# 7006268-0-0.net
KiCad netlist of a schematic drawn in EAGLE
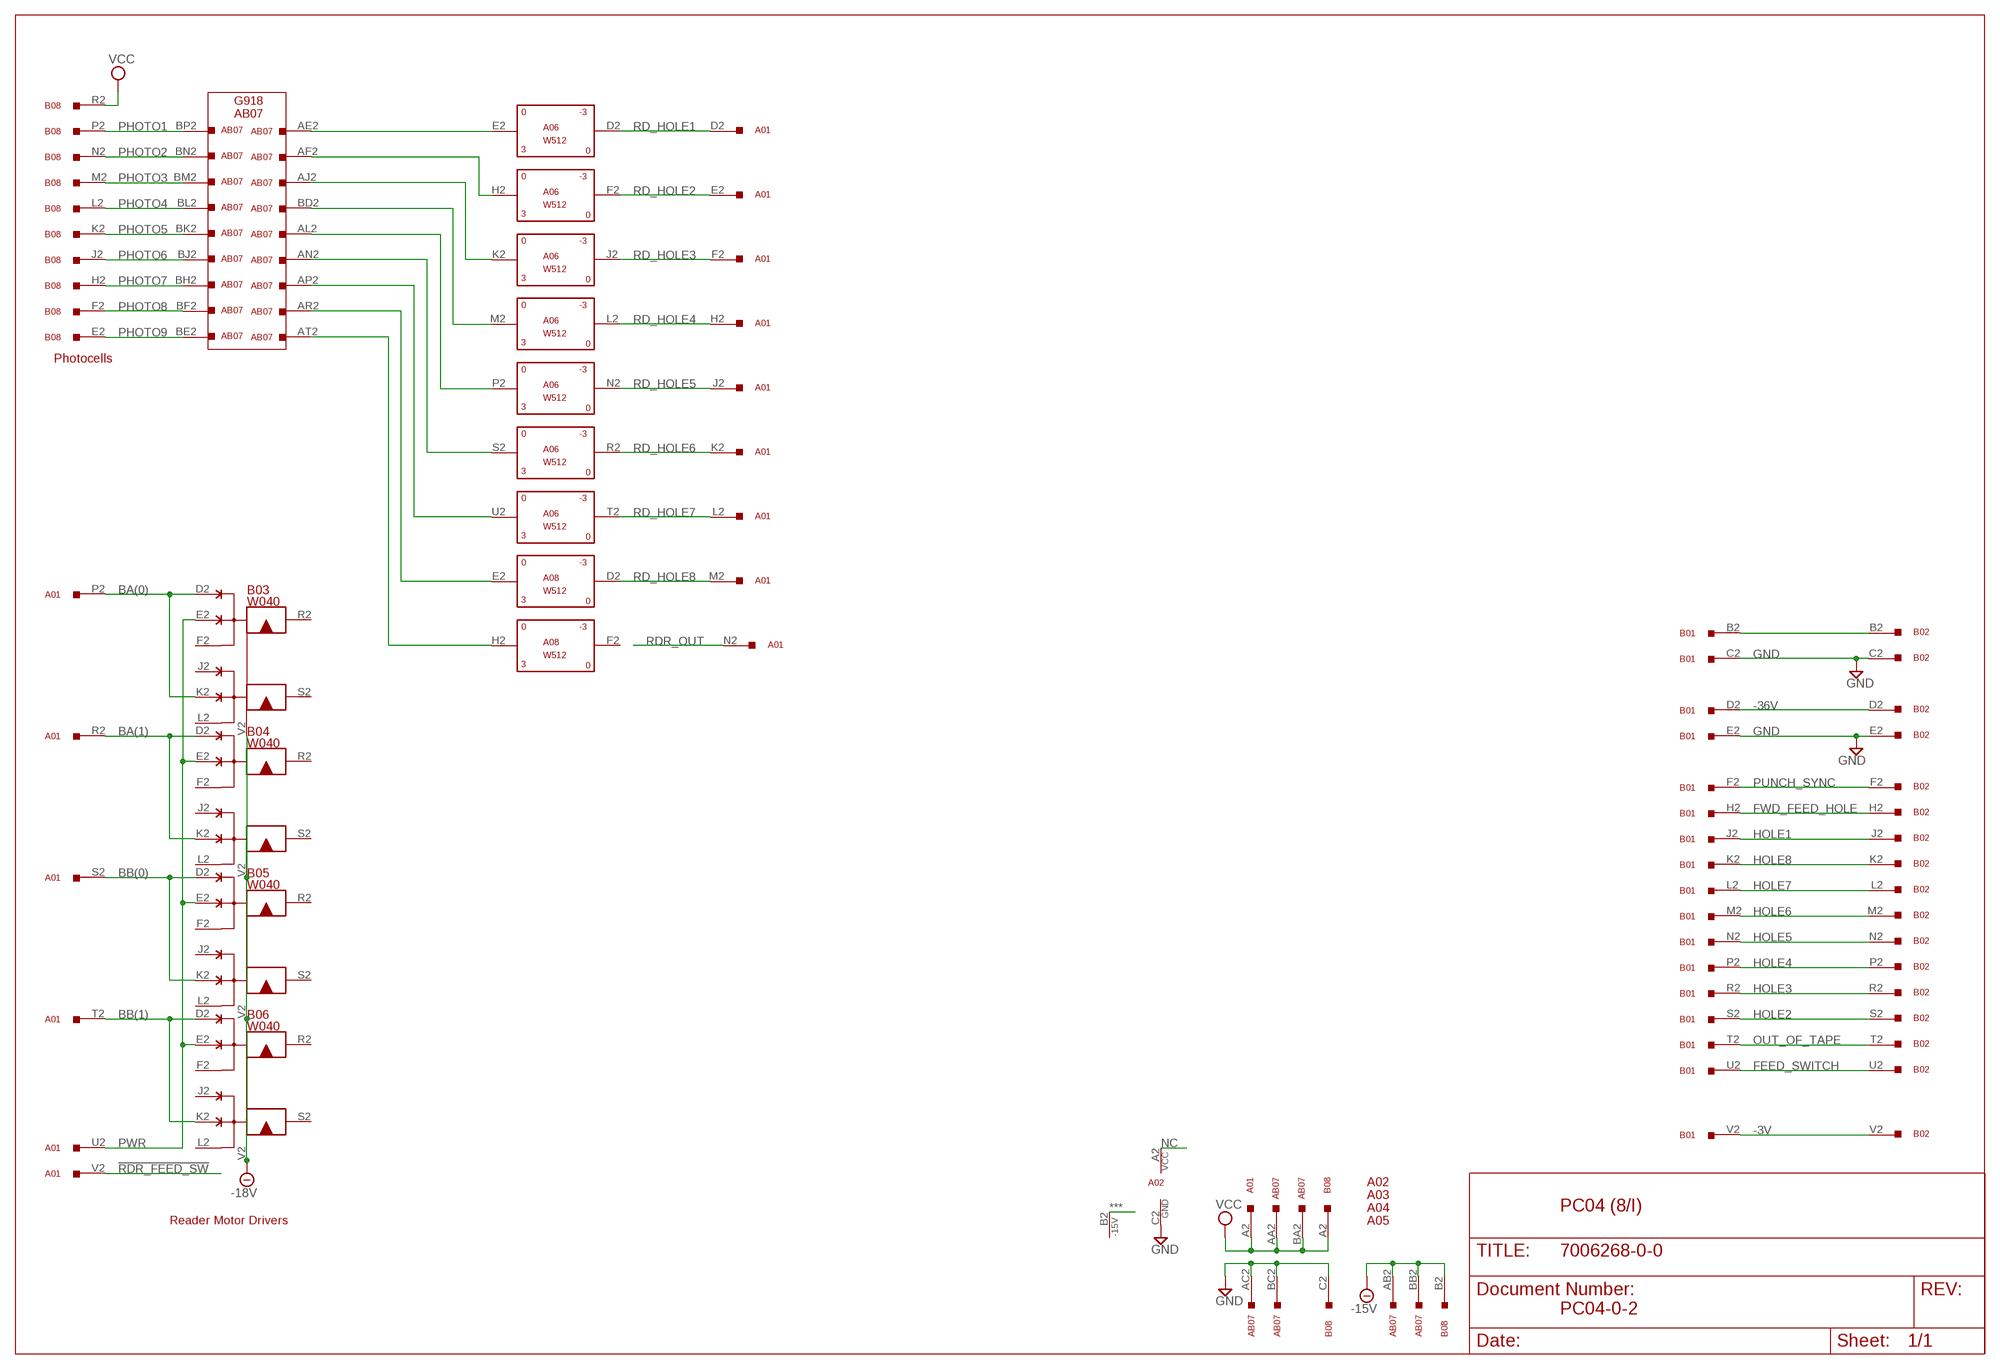
[diagram p0: schematic, sheet 1]

(export (version "E")
  (design (tool "Eeschema 10.0.6"))
  (components
    (comp (ref "A01")
      (value "W033")
      (footprint "eagle-import:H807")
      (libsource (lib "eagle-import") (part "W023"))
    )
    (comp (ref "A02")
      (value "EMPTY")
      (footprint "eagle-import:H807")
      (libsource (lib "eagle-import") (part "EMPTY"))
    )
    (comp (ref "A03")
      (value "EMPTY")
      (footprint "eagle-import:H807")
      (libsource (lib "eagle-import") (part "EMPTY"))
    )
    (comp (ref "A04")
      (value "EMPTY")
      (footprint "eagle-import:H807")
      (libsource (lib "eagle-import") (part "EMPTY"))
    )
    (comp (ref "A05")
      (value "EMPTY")
      (footprint "eagle-import:H807")
      (libsource (lib "eagle-import") (part "EMPTY"))
    )
    (comp (ref "A06")
      (value "W512")
      (footprint "eagle-import:H807")
      (libsource (lib "eagle-import") (part "W512"))
    )
    (comp (ref "A08")
      (value "W512")
      (footprint "eagle-import:H807")
      (libsource (lib "eagle-import") (part "W512"))
    )
    (comp (ref "AB07")
      (value "G918")
      (footprint "eagle-import:H807-2")
      (libsource (lib "eagle-import") (part "W991"))
    )
    (comp (ref "B01")
      (value "W033")
      (footprint "eagle-import:H807")
      (libsource (lib "eagle-import") (part "W023"))
    )
    (comp (ref "B02")
      (value "W033")
      (footprint "eagle-import:H807")
      (libsource (lib "eagle-import") (part "W023"))
    )
    (comp (ref "B03")
      (value "W040")
      (footprint "eagle-import:H807")
      (libsource (lib "eagle-import") (part "W040"))
    )
    (comp (ref "B04")
      (value "W040")
      (footprint "eagle-import:H807")
      (libsource (lib "eagle-import") (part "W040"))
    )
    (comp (ref "B05")
      (value "W040")
      (footprint "eagle-import:H807")
      (libsource (lib "eagle-import") (part "W040"))
    )
    (comp (ref "B06")
      (value "W040")
      (footprint "eagle-import:H807")
      (libsource (lib "eagle-import") (part "W040"))
    )
    (comp (ref "B08")
      (value "W033")
      (footprint "eagle-import:H807")
      (libsource (lib "eagle-import") (part "W023"))
    )
  )
  (nets
    (net (code "1") (name "-15V") (class "Default")
      (node (ref "AB07") (pin "AB2") (pinfunction "P$2_AB2") (pintype "bidirectional"))
      (node (ref "AB07") (pin "BB2") (pinfunction "P$2_BB2") (pintype "bidirectional"))
      (node (ref "B08") (pin "B2") (pinfunction "P$2_B2") (pintype "bidirectional"))
    )
    (net (code "2") (name "-18V") (class "Default")
      (node (ref "B03") (pin "V2") (pinfunction "V_V2") (pintype "input"))
      (node (ref "B04") (pin "V2") (pinfunction "V_V2") (pintype "input"))
      (node (ref "B05") (pin "V2") (pinfunction "V_V2") (pintype "input"))
      (node (ref "B06") (pin "V2") (pinfunction "V_V2") (pintype "input"))
    )
    (net (code "3") (name "/***") (class "Default")
      (node (ref "A02") (pin "B2") (pinfunction "-15V_B2") (pintype "power_in"))
    )
    (net (code "4") (name "/-3V") (class "Default")
      (node (ref "B01") (pin "V2") (pinfunction "P$2_V2") (pintype "bidirectional"))
      (node (ref "B02") (pin "V2") (pinfunction "P$2_V2") (pintype "bidirectional"))
    )
    (net (code "5") (name "/-36V") (class "Default")
      (node (ref "B01") (pin "D2") (pinfunction "P$2_D2") (pintype "bidirectional"))
      (node (ref "B02") (pin "D2") (pinfunction "P$2_D2") (pintype "bidirectional"))
    )
    (net (code "6") (name "/BA(0)") (class "Default")
      (node (ref "A01") (pin "P2") (pinfunction "P$2_P2") (pintype "bidirectional"))
      (node (ref "B03") (pin "D2") (pinfunction "D_D2") (pintype "input"))
      (node (ref "B03") (pin "K2") (pinfunction "K_K2") (pintype "input"))
    )
    (net (code "7") (name "/BA(1)") (class "Default")
      (node (ref "A01") (pin "R2") (pinfunction "P$2_R2") (pintype "bidirectional"))
      (node (ref "B04") (pin "D2") (pinfunction "D_D2") (pintype "input"))
      (node (ref "B04") (pin "K2") (pinfunction "K_K2") (pintype "input"))
    )
    (net (code "8") (name "/BB(0)") (class "Default")
      (node (ref "A01") (pin "S2") (pinfunction "P$2_S2") (pintype "bidirectional"))
      (node (ref "B05") (pin "D2") (pinfunction "D_D2") (pintype "input"))
      (node (ref "B05") (pin "K2") (pinfunction "K_K2") (pintype "input"))
    )
    (net (code "9") (name "/BB(1)") (class "Default")
      (node (ref "A01") (pin "T2") (pinfunction "P$2_T2") (pintype "bidirectional"))
      (node (ref "B06") (pin "D2") (pinfunction "D_D2") (pintype "input"))
      (node (ref "B06") (pin "K2") (pinfunction "K_K2") (pintype "input"))
    )
    (net (code "10") (name "/FEED_SWITCH") (class "Default")
      (node (ref "B01") (pin "U2") (pinfunction "P$2_U2") (pintype "bidirectional"))
      (node (ref "B02") (pin "U2") (pinfunction "P$2_U2") (pintype "bidirectional"))
    )
    (net (code "11") (name "/FWD_FEED_HOLE") (class "Default")
      (node (ref "B01") (pin "H2") (pinfunction "P$2_H2") (pintype "bidirectional"))
      (node (ref "B02") (pin "H2") (pinfunction "P$2_H2") (pintype "bidirectional"))
    )
    (net (code "12") (name "/HOLE1") (class "Default")
      (node (ref "B01") (pin "J2") (pinfunction "P$2_J2") (pintype "bidirectional"))
      (node (ref "B02") (pin "J2") (pinfunction "P$2_J2") (pintype "bidirectional"))
    )
    (net (code "13") (name "/HOLE2") (class "Default")
      (node (ref "B01") (pin "S2") (pinfunction "P$2_S2") (pintype "bidirectional"))
      (node (ref "B02") (pin "S2") (pinfunction "P$2_S2") (pintype "bidirectional"))
    )
    (net (code "14") (name "/HOLE3") (class "Default")
      (node (ref "B01") (pin "R2") (pinfunction "P$2_R2") (pintype "bidirectional"))
      (node (ref "B02") (pin "R2") (pinfunction "P$2_R2") (pintype "bidirectional"))
    )
    (net (code "15") (name "/HOLE4") (class "Default")
      (node (ref "B01") (pin "P2") (pinfunction "P$2_P2") (pintype "bidirectional"))
      (node (ref "B02") (pin "P2") (pinfunction "P$2_P2") (pintype "bidirectional"))
    )
    (net (code "16") (name "/HOLE5") (class "Default")
      (node (ref "B01") (pin "N2") (pinfunction "P$2_N2") (pintype "bidirectional"))
      (node (ref "B02") (pin "N2") (pinfunction "P$2_N2") (pintype "bidirectional"))
    )
    (net (code "17") (name "/HOLE6") (class "Default")
      (node (ref "B01") (pin "M2") (pinfunction "P$2_M2") (pintype "bidirectional"))
      (node (ref "B02") (pin "M2") (pinfunction "P$2_M2") (pintype "bidirectional"))
    )
    (net (code "18") (name "/HOLE7") (class "Default")
      (node (ref "B01") (pin "L2") (pinfunction "P$2_L2") (pintype "bidirectional"))
      (node (ref "B02") (pin "L2") (pinfunction "P$2_L2") (pintype "bidirectional"))
    )
    (net (code "19") (name "/HOLE8") (class "Default")
      (node (ref "B01") (pin "K2") (pinfunction "P$2_K2") (pintype "bidirectional"))
      (node (ref "B02") (pin "K2") (pinfunction "P$2_K2") (pintype "bidirectional"))
    )
    (net (code "20") (name "/NC") (class "Default")
      (node (ref "A02") (pin "A2") (pinfunction "VCC_A2") (pintype "power_in"))
    )
    (net (code "21") (name "/OUT_OF_TAPE") (class "Default")
      (node (ref "B01") (pin "T2") (pinfunction "P$2_T2") (pintype "bidirectional"))
      (node (ref "B02") (pin "T2") (pinfunction "P$2_T2") (pintype "bidirectional"))
    )
    (net (code "22") (name "/PHOTO1") (class "Default")
      (node (ref "AB07") (pin "BP2") (pinfunction "P$2_BP2") (pintype "bidirectional"))
      (node (ref "B08") (pin "P2") (pinfunction "P$2_P2") (pintype "bidirectional"))
    )
    (net (code "23") (name "/PHOTO2") (class "Default")
      (node (ref "AB07") (pin "BN2") (pinfunction "P$2_BN2") (pintype "bidirectional"))
      (node (ref "B08") (pin "N2") (pinfunction "P$2_N2") (pintype "bidirectional"))
    )
    (net (code "24") (name "/PHOTO3") (class "Default")
      (node (ref "AB07") (pin "BM2") (pinfunction "P$2_BM2") (pintype "bidirectional"))
      (node (ref "B08") (pin "M2") (pinfunction "P$2_M2") (pintype "bidirectional"))
    )
    (net (code "25") (name "/PHOTO4") (class "Default")
      (node (ref "AB07") (pin "BL2") (pinfunction "P$2_BL2") (pintype "bidirectional"))
      (node (ref "B08") (pin "L2") (pinfunction "P$2_L2") (pintype "bidirectional"))
    )
    (net (code "26") (name "/PHOTO5") (class "Default")
      (node (ref "AB07") (pin "BK2") (pinfunction "P$2_BK2") (pintype "bidirectional"))
      (node (ref "B08") (pin "K2") (pinfunction "P$2_K2") (pintype "bidirectional"))
    )
    (net (code "27") (name "/PHOTO6") (class "Default")
      (node (ref "AB07") (pin "BJ2") (pinfunction "P$2_BJ2") (pintype "bidirectional"))
      (node (ref "B08") (pin "J2") (pinfunction "P$2_J2") (pintype "bidirectional"))
    )
    (net (code "28") (name "/PHOTO7") (class "Default")
      (node (ref "AB07") (pin "BH2") (pinfunction "P$2_BH2") (pintype "bidirectional"))
      (node (ref "B08") (pin "H2") (pinfunction "P$2_H2") (pintype "bidirectional"))
    )
    (net (code "29") (name "/PHOTO8") (class "Default")
      (node (ref "AB07") (pin "BF2") (pinfunction "P$2_BF2") (pintype "bidirectional"))
      (node (ref "B08") (pin "F2") (pinfunction "P$2_F2") (pintype "bidirectional"))
    )
    (net (code "30") (name "/PHOTO9") (class "Default")
      (node (ref "AB07") (pin "BE2") (pinfunction "P$2_BE2") (pintype "bidirectional"))
      (node (ref "B08") (pin "E2") (pinfunction "P$2_E2") (pintype "bidirectional"))
    )
    (net (code "31") (name "/PUNCH_SYNC") (class "Default")
      (node (ref "B01") (pin "F2") (pinfunction "P$2_F2") (pintype "bidirectional"))
      (node (ref "B02") (pin "F2") (pinfunction "P$2_F2") (pintype "bidirectional"))
    )
    (net (code "32") (name "/PWR") (class "Default")
      (node (ref "A01") (pin "U2") (pinfunction "P$2_U2") (pintype "bidirectional"))
      (node (ref "B03") (pin "E2") (pinfunction "E_E2") (pintype "input"))
      (node (ref "B04") (pin "E2") (pinfunction "E_E2") (pintype "input"))
      (node (ref "B05") (pin "E2") (pinfunction "E_E2") (pintype "input"))
      (node (ref "B06") (pin "E2") (pinfunction "E_E2") (pintype "input"))
    )
    (net (code "33") (name "/RDR_OUT") (class "Default")
      (node (ref "A01") (pin "N2") (pinfunction "P$2_N2") (pintype "bidirectional"))
    )
    (net (code "34") (name "/RD_HOLE1") (class "Default")
      (node (ref "A01") (pin "D2") (pinfunction "P$2_D2") (pintype "bidirectional"))
      (node (ref "A06") (pin "D2") (pinfunction "OUT_D2") (pintype "output"))
    )
    (net (code "35") (name "/RD_HOLE2") (class "Default")
      (node (ref "A01") (pin "E2") (pinfunction "P$2_E2") (pintype "bidirectional"))
      (node (ref "A06") (pin "F2") (pinfunction "OUT_F2") (pintype "output"))
    )
    (net (code "36") (name "/RD_HOLE3") (class "Default")
      (node (ref "A01") (pin "F2") (pinfunction "P$2_F2") (pintype "bidirectional"))
      (node (ref "A06") (pin "J2") (pinfunction "OUT_J2") (pintype "output"))
    )
    (net (code "37") (name "/RD_HOLE4") (class "Default")
      (node (ref "A01") (pin "H2") (pinfunction "P$2_H2") (pintype "bidirectional"))
      (node (ref "A06") (pin "L2") (pinfunction "OUT_L2") (pintype "output"))
    )
    (net (code "38") (name "/RD_HOLE5") (class "Default")
      (node (ref "A01") (pin "J2") (pinfunction "P$2_J2") (pintype "bidirectional"))
      (node (ref "A06") (pin "N2") (pinfunction "OUT_N2") (pintype "output"))
    )
    (net (code "39") (name "/RD_HOLE6") (class "Default")
      (node (ref "A01") (pin "K2") (pinfunction "P$2_K2") (pintype "bidirectional"))
      (node (ref "A06") (pin "R2") (pinfunction "OUT_R2") (pintype "output"))
    )
    (net (code "40") (name "/RD_HOLE7") (class "Default")
      (node (ref "A01") (pin "L2") (pinfunction "P$2_L2") (pintype "bidirectional"))
      (node (ref "A06") (pin "T2") (pinfunction "OUT_T2") (pintype "output"))
    )
    (net (code "41") (name "/RD_HOLE8") (class "Default")
      (node (ref "A01") (pin "M2") (pinfunction "P$2_M2") (pintype "bidirectional"))
      (node (ref "A08") (pin "D2") (pinfunction "OUT_D2") (pintype "output"))
    )
    (net (code "42") (name "/~{RDR_FEED_SW}") (class "Default")
      (node (ref "A01") (pin "V2") (pinfunction "P$2_V2") (pintype "bidirectional"))
    )
    (net (code "43") (name "GND") (class "Default")
      (node (ref "A02") (pin "C2") (pinfunction "GND_C2") (pintype "power_in"))
      (node (ref "AB07") (pin "AC2") (pinfunction "P$2_AC2") (pintype "bidirectional"))
      (node (ref "AB07") (pin "BC2") (pinfunction "P$2_BC2") (pintype "bidirectional"))
      (node (ref "B01") (pin "C2") (pinfunction "P$2_C2") (pintype "bidirectional"))
      (node (ref "B01") (pin "E2") (pinfunction "P$2_E2") (pintype "bidirectional"))
      (node (ref "B02") (pin "C2") (pinfunction "P$2_C2") (pintype "bidirectional"))
      (node (ref "B02") (pin "E2") (pinfunction "P$2_E2") (pintype "bidirectional"))
      (node (ref "B08") (pin "C2") (pinfunction "P$2_C2") (pintype "bidirectional"))
    )
    (net (code "44") (name "Net-(A06A-IN)") (class "Default")
      (node (ref "A06") (pin "E2") (pinfunction "IN_E2") (pintype "input"))
      (node (ref "AB07") (pin "AE2") (pinfunction "P$2_AE2") (pintype "bidirectional"))
    )
    (net (code "45") (name "Net-(A06B-IN)") (class "Default")
      (node (ref "A06") (pin "H2") (pinfunction "IN_H2") (pintype "input"))
      (node (ref "AB07") (pin "AF2") (pinfunction "P$2_AF2") (pintype "bidirectional"))
    )
    (net (code "46") (name "Net-(A06E-IN)") (class "Default")
      (node (ref "A06") (pin "K2") (pinfunction "IN_K2") (pintype "input"))
      (node (ref "AB07") (pin "AJ2") (pinfunction "P$2_AJ2") (pintype "bidirectional"))
    )
    (net (code "47") (name "Net-(A06F-IN)") (class "Default")
      (node (ref "A06") (pin "M2") (pinfunction "IN_M2") (pintype "input"))
      (node (ref "AB07") (pin "BD2") (pinfunction "P$2_BD2") (pintype "bidirectional"))
    )
    (net (code "48") (name "Net-(A06G-IN)") (class "Default")
      (node (ref "A06") (pin "P2") (pinfunction "IN_P2") (pintype "input"))
      (node (ref "AB07") (pin "AL2") (pinfunction "P$2_AL2") (pintype "bidirectional"))
    )
    (net (code "49") (name "Net-(A06H-IN)") (class "Default")
      (node (ref "A06") (pin "S2") (pinfunction "IN_S2") (pintype "input"))
      (node (ref "AB07") (pin "AN2") (pinfunction "P$2_AN2") (pintype "bidirectional"))
    )
    (net (code "50") (name "Net-(A06I-IN)") (class "Default")
      (node (ref "A06") (pin "U2") (pinfunction "IN_U2") (pintype "input"))
      (node (ref "AB07") (pin "AP2") (pinfunction "P$2_AP2") (pintype "bidirectional"))
    )
    (net (code "51") (name "Net-(A08A-IN)") (class "Default")
      (node (ref "A08") (pin "E2") (pinfunction "IN_E2") (pintype "input"))
      (node (ref "AB07") (pin "AR2") (pinfunction "P$2_AR2") (pintype "bidirectional"))
    )
    (net (code "52") (name "Net-(A08B-IN)") (class "Default")
      (node (ref "A08") (pin "H2") (pinfunction "IN_H2") (pintype "input"))
      (node (ref "AB07") (pin "AT2") (pinfunction "P$2_AT2") (pintype "bidirectional"))
    )
    (net (code "53") (name "Net-(B01B-P$2)") (class "Default")
      (node (ref "B01") (pin "B2") (pinfunction "P$2_B2") (pintype "bidirectional"))
      (node (ref "B02") (pin "B2") (pinfunction "P$2_B2") (pintype "bidirectional"))
    )
    (net (code "54") (name "VCC") (class "Default")
      (node (ref "A01") (pin "A2") (pinfunction "P$2_A2") (pintype "bidirectional"))
      (node (ref "AB07") (pin "AA2") (pinfunction "P$2_AA2") (pintype "bidirectional"))
      (node (ref "AB07") (pin "BA2") (pinfunction "P$2_BA2") (pintype "bidirectional"))
      (node (ref "B08") (pin "A2") (pinfunction "P$2_A2") (pintype "bidirectional"))
      (node (ref "B08") (pin "R2") (pinfunction "P$2_R2") (pintype "bidirectional"))
    )
    (net (code "55") (name "unconnected-(A08B-OUT-PadF2)") (class "Default")
      (node (ref "A08") (pin "F2") (pinfunction "OUT_F2") (pintype "output"))
    )
    (net (code "56") (name "unconnected-(B03A-F-PadF2)") (class "Default")
      (node (ref "B03") (pin "F2") (pinfunction "F_F2") (pintype "passive"))
    )
    (net (code "57") (name "unconnected-(B03A-J-PadJ2)") (class "Default")
      (node (ref "B03") (pin "J2") (pinfunction "J_J2") (pintype "input"))
    )
    (net (code "58") (name "unconnected-(B03A-L-PadL2)") (class "Default")
      (node (ref "B03") (pin "L2") (pinfunction "L_L2") (pintype "passive"))
    )
    (net (code "59") (name "unconnected-(B03A-R-PadR2)") (class "Default")
      (node (ref "B03") (pin "R2") (pinfunction "R_R2") (pintype "open_collector"))
    )
    (net (code "60") (name "unconnected-(B03A-S-PadS2)") (class "Default")
      (node (ref "B03") (pin "S2") (pinfunction "S_S2") (pintype "open_collector"))
    )
    (net (code "61") (name "unconnected-(B04A-F-PadF2)") (class "Default")
      (node (ref "B04") (pin "F2") (pinfunction "F_F2") (pintype "passive"))
    )
    (net (code "62") (name "unconnected-(B04A-J-PadJ2)") (class "Default")
      (node (ref "B04") (pin "J2") (pinfunction "J_J2") (pintype "input"))
    )
    (net (code "63") (name "unconnected-(B04A-L-PadL2)") (class "Default")
      (node (ref "B04") (pin "L2") (pinfunction "L_L2") (pintype "passive"))
    )
    (net (code "64") (name "unconnected-(B04A-R-PadR2)") (class "Default")
      (node (ref "B04") (pin "R2") (pinfunction "R_R2") (pintype "open_collector"))
    )
    (net (code "65") (name "unconnected-(B04A-S-PadS2)") (class "Default")
      (node (ref "B04") (pin "S2") (pinfunction "S_S2") (pintype "open_collector"))
    )
    (net (code "66") (name "unconnected-(B05A-F-PadF2)") (class "Default")
      (node (ref "B05") (pin "F2") (pinfunction "F_F2") (pintype "passive"))
    )
    (net (code "67") (name "unconnected-(B05A-J-PadJ2)") (class "Default")
      (node (ref "B05") (pin "J2") (pinfunction "J_J2") (pintype "input"))
    )
    (net (code "68") (name "unconnected-(B05A-L-PadL2)") (class "Default")
      (node (ref "B05") (pin "L2") (pinfunction "L_L2") (pintype "passive"))
    )
    (net (code "69") (name "unconnected-(B05A-R-PadR2)") (class "Default")
      (node (ref "B05") (pin "R2") (pinfunction "R_R2") (pintype "open_collector"))
    )
    (net (code "70") (name "unconnected-(B05A-S-PadS2)") (class "Default")
      (node (ref "B05") (pin "S2") (pinfunction "S_S2") (pintype "open_collector"))
    )
    (net (code "71") (name "unconnected-(B06A-F-PadF2)") (class "Default")
      (node (ref "B06") (pin "F2") (pinfunction "F_F2") (pintype "passive"))
    )
    (net (code "72") (name "unconnected-(B06A-J-PadJ2)") (class "Default")
      (node (ref "B06") (pin "J2") (pinfunction "J_J2") (pintype "input"))
    )
    (net (code "73") (name "unconnected-(B06A-L-PadL2)") (class "Default")
      (node (ref "B06") (pin "L2") (pinfunction "L_L2") (pintype "passive"))
    )
    (net (code "74") (name "unconnected-(B06A-R-PadR2)") (class "Default")
      (node (ref "B06") (pin "R2") (pinfunction "R_R2") (pintype "open_collector"))
    )
    (net (code "75") (name "unconnected-(B06A-S-PadS2)") (class "Default")
      (node (ref "B06") (pin "S2") (pinfunction "S_S2") (pintype "open_collector"))
    )
  )
)
